# Sheet1.net
KiCad netlist of a schematic drawn in Altium Designer
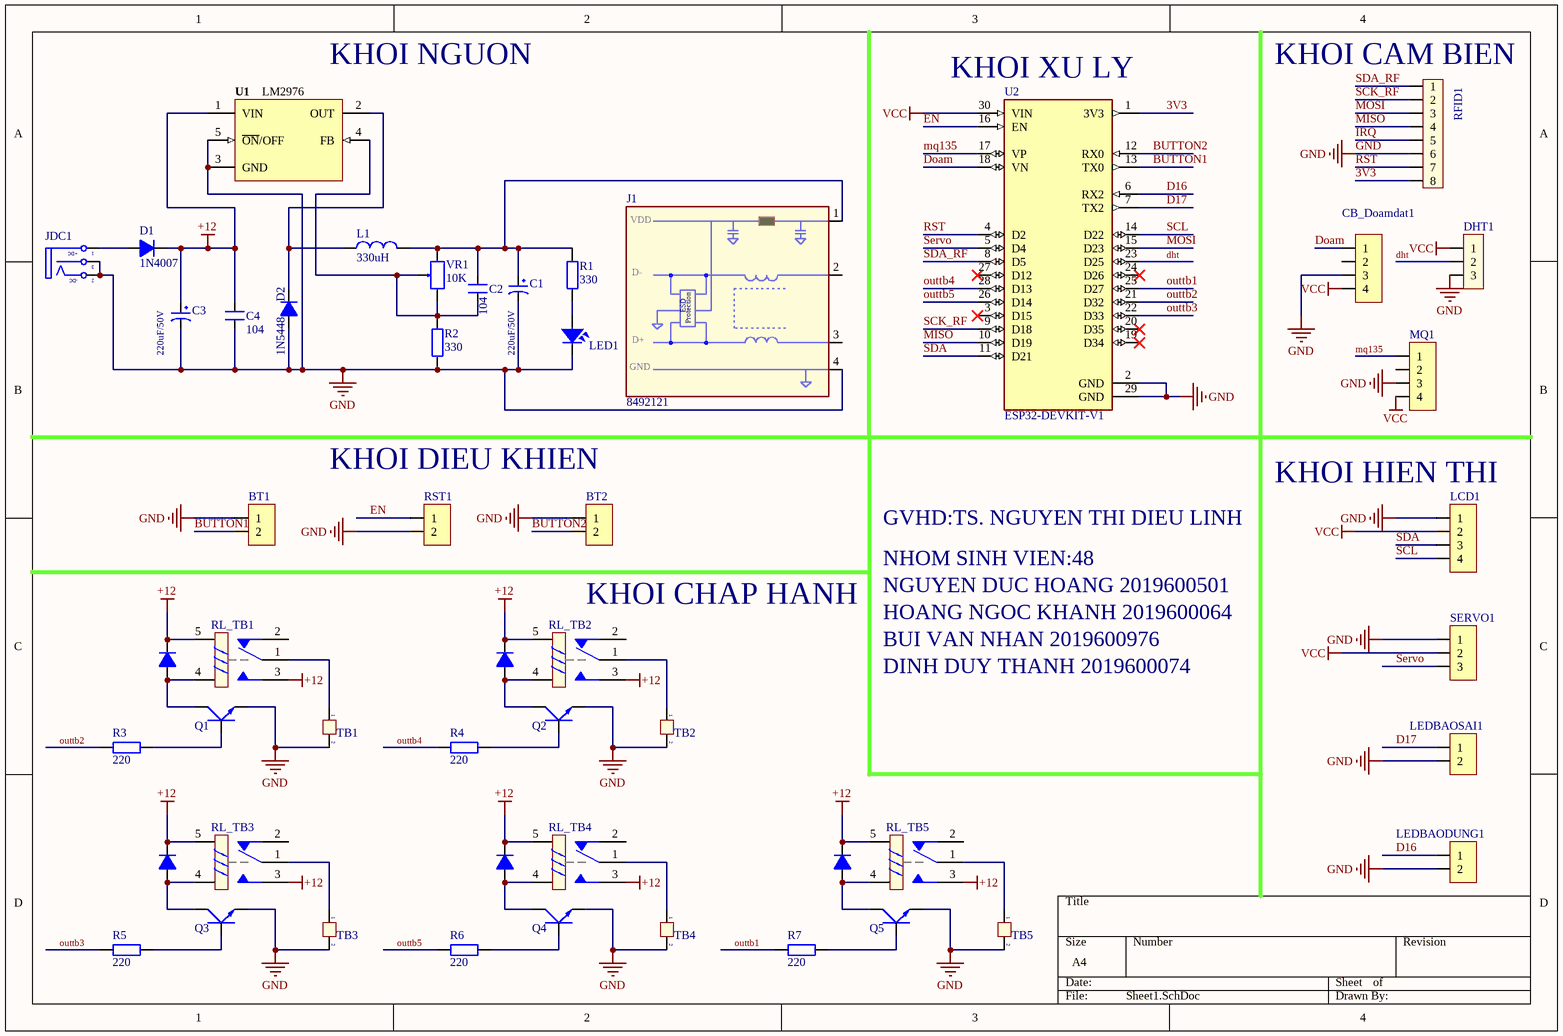
[diagram p0: Sheet1.SchDoc]

(export (version "E")
  (design (tool "Eeschema 10.0.6"))
  (components
    (comp (ref "BT1")
      (value "JP2")
      (footprint "JP2-C1T")
      (description "WR-PHD 2.54 mm Angled Socket Header")
      (fields
        (field (name "MANUFACTURER") "Würth Elektronik eiSos GmbH")
        (field (name "PARTNO") "613002143121")
        (field (name "CREATED BY") "Karrer Zheng")
      )
      (libsource (lib "thuviencuatu") (part "JP2"))
    )
    (comp (ref "BT2")
      (value "JP2")
      (footprint "JP2-C1T")
      (description "WR-PHD 2.54 mm Angled Socket Header")
      (fields
        (field (name "MANUFACTURER") "Würth Elektronik eiSos GmbH")
        (field (name "PARTNO") "613002143121")
        (field (name "CREATED BY") "Karrer Zheng")
      )
      (libsource (lib "thuviencuatu") (part "JP2"))
    )
    (comp (ref "C1")
      (value "220uF/50V")
      (footprint "CP1.5/3.4")
      (description "Cap 1000uF/16V - 220uF/50V")
      (libsource (lib "Thuvien3D") (part "CP4"))
    )
    (comp (ref "C2")
      (value "104")
      (footprint "CN1")
      (description "Cap np  1pF - 472pF")
      (libsource (lib "Thuvien3D") (part "CN1"))
    )
    (comp (ref "C3")
      (value "220uF/50V")
      (footprint "CP1.5/3.4")
      (description "Cap 1000uF/16V - 220uF/50V")
      (libsource (lib "Thuvien3D") (part "CP4"))
    )
    (comp (ref "C4")
      (value "104")
      (footprint "CN1")
      (description "Cap np  1pF - 472pF")
      (libsource (lib "Thuvien3D") (part "CN1"))
    )
    (comp (ref "CB_Doamdat1")
      (value "JP4")
      (footprint "JP4-C1T")
      (description "WR-PHD 2.54 mm Angled Socket Header")
      (fields
        (field (name "MANUFACTURER") "Würth Elektronik eiSos GmbH")
        (field (name "PARTNO") "613004143121")
        (field (name "CREATED BY") "Karrer Zheng")
      )
      (libsource (lib "thuviencuatu") (part "JP4"))
    )
    (comp (ref "D1")
      (value "1N4007")
      (footprint "D1A")
      (description "Diode 1A")
      (libsource (lib "Thuvien3D") (part "D1A"))
    )
    (comp (ref "D2")
      (value "1N5448")
      (footprint "D1A")
      (description "Diode 1A")
      (libsource (lib "Thuvien3D") (part "D1A"))
    )
    (comp (ref "D3")
      (value "1N4007")
      (footprint "D2A")
      (description "Diode 1A")
      (libsource (lib "Thuvien3D") (part "D1A"))
    )
    (comp (ref "D4")
      (value "1N4007")
      (footprint "D2A")
      (description "Diode 1A")
      (libsource (lib "Thuvien3D") (part "D1A"))
    )
    (comp (ref "D5")
      (value "1N4007")
      (footprint "D2A")
      (description "Diode 1A")
      (libsource (lib "Thuvien3D") (part "D1A"))
    )
    (comp (ref "D6")
      (value "1N4007")
      (footprint "D2A")
      (description "Diode 1A")
      (libsource (lib "Thuvien3D") (part "D1A"))
    )
    (comp (ref "D7")
      (value "1N4007")
      (footprint "D2A")
      (description "Diode 1A")
      (libsource (lib "Thuvien3D") (part "D1A"))
    )
    (comp (ref "DHT1") (value "Jumper 3") (footprint "JP3") (libsource (lib "Thuvien3D") (part "JP3")))
    (comp (ref "J1")
      (value "8492121")
      (footprint "USB-C1")
      (description "THT USB 2.0 A Connector WE-EPLE")
      (fields
        (field (name "MANUFACTURER") "Würth Elektronik eiSos GmbH")
        (field (name "CREATED BY") "Christin Otto")
      )
      (libsource (lib "thuviencuatu") (part "USB-4"))
    )
    (comp (ref "JDC1")
      (value "Jac DC")
      (footprint "DC-IN")
      (description "Jac DC input")
      (libsource (lib "Thuvien3D") (part "DCIN"))
    )
    (comp (ref "L1")
      (value "330uH")
      (footprint "L01")
      (description "Inductor")
      (libsource (lib "Thuvien3D") (part "L1"))
    )
    (comp (ref "LCD1")
      (value "JP4")
      (footprint "JP4-C1T")
      (description "WR-PHD 2.54 mm Angled Socket Header")
      (fields
        (field (name "MANUFACTURER") "Würth Elektronik eiSos GmbH")
        (field (name "PARTNO") "613004143121")
        (field (name "CREATED BY") "Karrer Zheng")
      )
      (libsource (lib "thuviencuatu") (part "JP4"))
    )
    (comp (ref "LED1")
      (value "LED")
      (footprint "LED-3")
      (description "LED Single colour Green and Red")
      (libsource (lib "Thuvien3D") (part "LED"))
    )
    (comp (ref "LEDBAODUNG1")
      (value "JP2")
      (footprint "JP2-C1T")
      (description "WR-PHD 2.54 mm Angled Socket Header")
      (fields
        (field (name "MANUFACTURER") "Würth Elektronik eiSos GmbH")
        (field (name "PARTNO") "613002143121")
        (field (name "CREATED BY") "Karrer Zheng")
      )
      (libsource (lib "thuviencuatu") (part "JP2"))
    )
    (comp (ref "LEDBAOSAI1")
      (value "JP2")
      (footprint "JP2-C1T")
      (description "WR-PHD 2.54 mm Angled Socket Header")
      (fields
        (field (name "MANUFACTURER") "Würth Elektronik eiSos GmbH")
        (field (name "PARTNO") "613002143121")
        (field (name "CREATED BY") "Karrer Zheng")
      )
      (libsource (lib "thuviencuatu") (part "JP2"))
    )
    (comp (ref "MQ1")
      (value "JP4")
      (footprint "JP4-C1T")
      (description "WR-PHD 2.54 mm Angled Socket Header")
      (fields
        (field (name "MANUFACTURER") "Würth Elektronik eiSos GmbH")
        (field (name "PARTNO") "613004143121")
        (field (name "CREATED BY") "Karrer Zheng")
      )
      (libsource (lib "thuviencuatu") (part "JP4"))
    )
    (comp (ref "Q1")
      (value "C1815")
      (footprint "QTO-92")
      (description "NPN 600mW, ECB")
      (libsource (lib "Thuvien3D") (part "C1815"))
    )
    (comp (ref "Q2")
      (value "C1815")
      (footprint "QTO-92")
      (description "NPN 600mW, ECB")
      (libsource (lib "Thuvien3D") (part "C1815"))
    )
    (comp (ref "Q3")
      (value "C1815")
      (footprint "QTO-92")
      (description "NPN 600mW, ECB")
      (libsource (lib "Thuvien3D") (part "C1815"))
    )
    (comp (ref "Q4")
      (value "C1815")
      (footprint "QTO-92")
      (description "NPN 600mW, ECB")
      (libsource (lib "Thuvien3D") (part "C1815"))
    )
    (comp (ref "Q5")
      (value "C1815")
      (footprint "QTO-92")
      (description "NPN 600mW, ECB")
      (libsource (lib "Thuvien3D") (part "C1815"))
    )
    (comp (ref "R1")
      (value "330")
      (footprint "R1/2W")
      (description "Resistor 1/4W")
      (libsource (lib "Thuvien3D") (part "R1/4W"))
    )
    (comp (ref "R2")
      (value "330")
      (footprint "R1/2W")
      (description "Resistor 1/4W")
      (libsource (lib "Thuvien3D") (part "R1/4W"))
    )
    (comp (ref "R3")
      (value "220")
      (footprint "R1/2W")
      (description "Resistor 1/4W")
      (libsource (lib "Thuvien3D") (part "R1/4W"))
    )
    (comp (ref "R4")
      (value "220")
      (footprint "R1/2W")
      (description "Resistor 1/4W")
      (libsource (lib "Thuvien3D") (part "R1/4W"))
    )
    (comp (ref "R5")
      (value "220")
      (footprint "R1/2W")
      (description "Resistor 1/4W")
      (libsource (lib "Thuvien3D") (part "R1/4W"))
    )
    (comp (ref "R6")
      (value "220")
      (footprint "R1/2W")
      (description "Resistor 1/4W")
      (libsource (lib "Thuvien3D") (part "R1/4W"))
    )
    (comp (ref "R7")
      (value "220")
      (footprint "R1/2W")
      (description "Resistor 1/4W")
      (libsource (lib "Thuvien3D") (part "R1/4W"))
    )
    (comp (ref "RFID1") (value "JP8 PIN") (footprint "JP8") (libsource (lib "syhaunguyen") (part "JP8")))
    (comp (ref "RL_TB1")
      (value "Relay1")
      (footprint "RL_SPDT_10A")
      (description "Relay SPDT,10A - 12VDC 5 Pin")
      (libsource (lib "Thuvien3D") (part "Relay 1"))
    )
    (comp (ref "RL_TB2")
      (value "Relay1")
      (footprint "RL_SPDT_10A")
      (description "Relay SPDT,10A - 12VDC 5 Pin")
      (libsource (lib "Thuvien3D") (part "Relay 1"))
    )
    (comp (ref "RL_TB3")
      (value "Relay1")
      (footprint "RL_SPDT_10A")
      (description "Relay SPDT,10A - 12VDC 5 Pin")
      (libsource (lib "Thuvien3D") (part "Relay 1"))
    )
    (comp (ref "RL_TB4")
      (value "Relay1")
      (footprint "RL_SPDT_10A")
      (description "Relay SPDT,10A - 12VDC 5 Pin")
      (libsource (lib "Thuvien3D") (part "Relay 1"))
    )
    (comp (ref "RL_TB5")
      (value "Relay1")
      (footprint "RL_SPDT_10A")
      (description "Relay SPDT,10A - 12VDC 5 Pin")
      (libsource (lib "Thuvien3D") (part "Relay 1"))
    )
    (comp (ref "RST1")
      (value "JP2")
      (footprint "JP2-C1T")
      (description "WR-PHD 2.54 mm Angled Socket Header")
      (fields
        (field (name "MANUFACTURER") "Würth Elektronik eiSos GmbH")
        (field (name "PARTNO") "613002143121")
        (field (name "CREATED BY") "Karrer Zheng")
      )
      (libsource (lib "thuviencuatu") (part "JP2"))
    )
    (comp (ref "SERVO1")
      (value "JP3")
      (footprint "JP3-C1T")
      (description "WR-PHD 2.54 mm Angled Socket Header")
      (fields
        (field (name "MANUFACTURER") "Würth Elektronik eiSos GmbH")
        (field (name "PARTNO") "613003143121")
        (field (name "CREATED BY") "Karrer Zheng")
      )
      (libsource (lib "thuviencuatu") (part "JP3"))
    )
    (comp (ref "TB1") (value "Jumper 2") (footprint "JP2") (libsource (lib "Thuvien3D") (part "JP 2")))
    (comp (ref "TB2") (value "Jumper 2") (footprint "JP2") (libsource (lib "Thuvien3D") (part "JP 2")))
    (comp (ref "TB3") (value "Jumper 2") (footprint "JP2") (libsource (lib "Thuvien3D") (part "JP 2")))
    (comp (ref "TB4") (value "Jumper 2") (footprint "JP2") (libsource (lib "Thuvien3D") (part "JP 2")))
    (comp (ref "TB5") (value "Jumper 2") (footprint "JP2") (libsource (lib "Thuvien3D") (part "JP 2")))
    (comp (ref "U1") (value "LM2976") (footprint "DIP5-T") (libsource (lib "thuviencuatu") (part "LM2596")))
    (comp (ref "U2")
      (value "ESP32-DEVKIT-V1")
      (footprint "MODULE_ESP32_DEVKIT_V1")
      (fields (field (name "MF") "Do it"))
      (libsource (lib "ESP32-DEVKIT-V1") (part "ESP32-DEVKIT-V1"))
    )
    (comp (ref "VR1")
      (value "10K")
      (footprint "VR")
      (description "Var Resistor")
      (libsource (lib "Thuvien3D") (part "VR"))
    )
  )
  (nets
    (net (code "1") (name "+12") (class "Default")
      (node (ref "C3") (pin "1") (pinfunction "1_1") (pintype "passive"))
      (node (ref "C4") (pin "2") (pinfunction "2_2") (pintype "passive"))
      (node (ref "D1") (pin "2") (pinfunction "K_2") (pintype "passive"))
      (node (ref "D3") (pin "2") (pinfunction "K_2") (pintype "passive"))
      (node (ref "D4") (pin "2") (pinfunction "K_2") (pintype "passive"))
      (node (ref "D5") (pin "2") (pinfunction "K_2") (pintype "passive"))
      (node (ref "D6") (pin "2") (pinfunction "K_2") (pintype "passive"))
      (node (ref "D7") (pin "2") (pinfunction "K_2") (pintype "passive"))
      (node (ref "RL_TB1") (pin "3") (pinfunction "3_3") (pintype "passive"))
      (node (ref "RL_TB1") (pin "5") (pinfunction "5_5") (pintype "passive"))
      (node (ref "RL_TB2") (pin "3") (pinfunction "3_3") (pintype "passive"))
      (node (ref "RL_TB2") (pin "5") (pinfunction "5_5") (pintype "passive"))
      (node (ref "RL_TB3") (pin "3") (pinfunction "3_3") (pintype "passive"))
      (node (ref "RL_TB3") (pin "5") (pinfunction "5_5") (pintype "passive"))
      (node (ref "RL_TB4") (pin "3") (pinfunction "3_3") (pintype "passive"))
      (node (ref "RL_TB4") (pin "5") (pinfunction "5_5") (pintype "passive"))
      (node (ref "RL_TB5") (pin "3") (pinfunction "3_3") (pintype "passive"))
      (node (ref "RL_TB5") (pin "5") (pinfunction "5_5") (pintype "passive"))
      (node (ref "U1") (pin "1") (pinfunction "VIN_1") (pintype "power_in"))
    )
    (net (code "2") (name "/3V3") (class "Default")
      (node (ref "RFID1") (pin "8") (pinfunction "8_8") (pintype "passive"))
      (node (ref "U2") (pin "1") (pinfunction "3V3_1") (pintype "output"))
    )
    (net (code "3") (name "/BUTTON1") (class "Default")
      (node (ref "BT1") (pin "2") (pinfunction "2_2") (pintype "passive"))
      (node (ref "U2") (pin "13") (pinfunction "TX0_13") (pintype "output"))
    )
    (net (code "4") (name "/BUTTON2") (class "Default")
      (node (ref "BT2") (pin "2") (pinfunction "2_2") (pintype "passive"))
      (node (ref "U2") (pin "12") (pinfunction "RX0_12") (pintype "input"))
    )
    (net (code "5") (name "/D16") (class "Default")
      (node (ref "LEDBAODUNG1") (pin "1") (pinfunction "1_1") (pintype "passive"))
      (node (ref "U2") (pin "6") (pinfunction "RX2_6") (pintype "input"))
    )
    (net (code "6") (name "/D17") (class "Default")
      (node (ref "LEDBAOSAI1") (pin "1") (pinfunction "1_1") (pintype "passive"))
      (node (ref "U2") (pin "7") (pinfunction "TX2_7") (pintype "output"))
    )
    (net (code "7") (name "/Doam") (class "Default")
      (node (ref "CB_Doamdat1") (pin "1") (pinfunction "1_1") (pintype "passive"))
      (node (ref "U2") (pin "18") (pinfunction "VN_18") (pintype "bidirectional"))
    )
    (net (code "8") (name "/EN") (class "Default")
      (node (ref "RST1") (pin "1") (pinfunction "1_1") (pintype "passive"))
      (node (ref "U2") (pin "16") (pinfunction "EN_16") (pintype "input"))
    )
    (net (code "9") (name "/IRQ") (class "Default")
      (node (ref "RFID1") (pin "5") (pinfunction "5_5") (pintype "passive"))
    )
    (net (code "10") (name "/MISO") (class "Default")
      (node (ref "RFID1") (pin "4") (pinfunction "4_4") (pintype "passive"))
      (node (ref "U2") (pin "10") (pinfunction "D19_10") (pintype "bidirectional"))
    )
    (net (code "11") (name "/MOSI") (class "Default")
      (node (ref "RFID1") (pin "3") (pinfunction "3_3") (pintype "passive"))
      (node (ref "U2") (pin "15") (pinfunction "D23_15") (pintype "bidirectional"))
    )
    (net (code "12") (name "/RST") (class "Default")
      (node (ref "RFID1") (pin "7") (pinfunction "7_7") (pintype "passive"))
      (node (ref "U2") (pin "4") (pinfunction "D2_4") (pintype "bidirectional"))
    )
    (net (code "13") (name "/SCK_RF") (class "Default")
      (node (ref "RFID1") (pin "2") (pinfunction "2_2") (pintype "passive"))
      (node (ref "U2") (pin "9") (pinfunction "D18_9") (pintype "bidirectional"))
    )
    (net (code "14") (name "/SCL") (class "Default")
      (node (ref "LCD1") (pin "4") (pinfunction "4_4") (pintype "passive"))
      (node (ref "U2") (pin "14") (pinfunction "D22_14") (pintype "bidirectional"))
    )
    (net (code "15") (name "/SDA") (class "Default")
      (node (ref "LCD1") (pin "3") (pinfunction "3_3") (pintype "passive"))
      (node (ref "U2") (pin "11") (pinfunction "D21_11") (pintype "bidirectional"))
    )
    (net (code "16") (name "/SDA_RF") (class "Default")
      (node (ref "RFID1") (pin "1") (pinfunction "1_1") (pintype "passive"))
      (node (ref "U2") (pin "8") (pinfunction "D5_8") (pintype "bidirectional"))
    )
    (net (code "17") (name "/Servo") (class "Default")
      (node (ref "SERVO1") (pin "3") (pinfunction "3_3") (pintype "passive"))
      (node (ref "U2") (pin "5") (pinfunction "D4_5") (pintype "bidirectional"))
    )
    (net (code "18") (name "/dht") (class "Default")
      (node (ref "DHT1") (pin "2") (pinfunction "2_2") (pintype "passive"))
      (node (ref "U2") (pin "23") (pinfunction "D25_23") (pintype "bidirectional"))
    )
    (net (code "19") (name "/mq135") (class "Default")
      (node (ref "MQ1") (pin "1") (pinfunction "1_1") (pintype "passive"))
      (node (ref "U2") (pin "17") (pinfunction "VP_17") (pintype "bidirectional"))
    )
    (net (code "20") (name "/outtb1") (class "Default")
      (node (ref "R7") (pin "1") (pinfunction "1_1") (pintype "passive"))
      (node (ref "U2") (pin "25") (pinfunction "D27_25") (pintype "bidirectional"))
    )
    (net (code "21") (name "/outtb2") (class "Default")
      (node (ref "R3") (pin "1") (pinfunction "1_1") (pintype "passive"))
      (node (ref "U2") (pin "21") (pinfunction "D32_21") (pintype "bidirectional"))
    )
    (net (code "22") (name "/outtb3") (class "Default")
      (node (ref "R5") (pin "1") (pinfunction "1_1") (pintype "passive"))
      (node (ref "U2") (pin "22") (pinfunction "D33_22") (pintype "bidirectional"))
    )
    (net (code "23") (name "/outtb4") (class "Default")
      (node (ref "R4") (pin "1") (pinfunction "1_1") (pintype "passive"))
      (node (ref "U2") (pin "28") (pinfunction "D13_28") (pintype "bidirectional"))
    )
    (net (code "24") (name "/outtb5") (class "Default")
      (node (ref "R6") (pin "1") (pinfunction "1_1") (pintype "passive"))
      (node (ref "U2") (pin "26") (pinfunction "D14_26") (pintype "bidirectional"))
    )
    (net (code "25") (name "GND") (class "Default")
      (node (ref "BT1") (pin "1") (pinfunction "1_1") (pintype "passive"))
      (node (ref "BT2") (pin "1") (pinfunction "1_1") (pintype "passive"))
      (node (ref "C1") (pin "2") (pinfunction "2_2") (pintype "passive"))
      (node (ref "C3") (pin "2") (pinfunction "2_2") (pintype "passive"))
      (node (ref "C4") (pin "1") (pinfunction "1_1") (pintype "passive"))
      (node (ref "CB_Doamdat1") (pin "3") (pinfunction "3_3") (pintype "passive"))
      (node (ref "D2") (pin "1") (pinfunction "A_1") (pintype "passive"))
      (node (ref "DHT1") (pin "3") (pinfunction "3_3") (pintype "passive"))
      (node (ref "J1") (pin "4") (pinfunction "GND_4") (pintype "passive"))
      (node (ref "JDC1") (pin "2") (pinfunction "TN_2") (pintype "passive"))
      (node (ref "JDC1") (pin "3") (pinfunction "S_3") (pintype "power_in"))
      (node (ref "LCD1") (pin "1") (pinfunction "1_1") (pintype "passive"))
      (node (ref "LED1") (pin "2") (pinfunction "2_2") (pintype "passive"))
      (node (ref "LEDBAODUNG1") (pin "2") (pinfunction "2_2") (pintype "passive"))
      (node (ref "LEDBAOSAI1") (pin "2") (pinfunction "2_2") (pintype "passive"))
      (node (ref "MQ1") (pin "3") (pinfunction "3_3") (pintype "passive"))
      (node (ref "Q1") (pin "1") (pinfunction "E_1") (pintype "passive"))
      (node (ref "Q2") (pin "1") (pinfunction "E_1") (pintype "passive"))
      (node (ref "Q3") (pin "1") (pinfunction "E_1") (pintype "passive"))
      (node (ref "Q4") (pin "1") (pinfunction "E_1") (pintype "passive"))
      (node (ref "Q5") (pin "1") (pinfunction "E_1") (pintype "passive"))
      (node (ref "R2") (pin "1") (pinfunction "1_1") (pintype "passive"))
      (node (ref "RFID1") (pin "6") (pinfunction "6_6") (pintype "passive"))
      (node (ref "RST1") (pin "2") (pinfunction "2_2") (pintype "passive"))
      (node (ref "SERVO1") (pin "1") (pinfunction "1_1") (pintype "passive"))
      (node (ref "TB1") (pin "2") (pinfunction "2_2") (pintype "passive"))
      (node (ref "TB2") (pin "2") (pinfunction "2_2") (pintype "passive"))
      (node (ref "TB3") (pin "2") (pinfunction "2_2") (pintype "passive"))
      (node (ref "TB4") (pin "2") (pinfunction "2_2") (pintype "passive"))
      (node (ref "TB5") (pin "2") (pinfunction "2_2") (pintype "passive"))
      (node (ref "U1") (pin "3") (pinfunction "GND_3") (pintype "power_in"))
      (node (ref "U1") (pin "5") (pinfunction "~{ON}/OFF_5") (pintype "input"))
      (node (ref "U2") (pin "2") (pinfunction "GND_2") (pintype "power_in"))
      (node (ref "U2") (pin "29") (pinfunction "GND_29") (pintype "power_in"))
    )
    (net (code "26") (name "Net-(D1-A)") (class "Default")
      (node (ref "D1") (pin "1") (pinfunction "A_1") (pintype "passive"))
      (node (ref "JDC1") (pin "1") (pinfunction "T_1") (pintype "passive"))
    )
    (net (code "27") (name "Net-(D2-K)") (class "Default")
      (node (ref "D2") (pin "2") (pinfunction "K_2") (pintype "passive"))
      (node (ref "L1") (pin "1") (pinfunction "1_1") (pintype "passive"))
      (node (ref "U1") (pin "2") (pinfunction "OUT_2") (pintype "power_in"))
    )
    (net (code "28") (name "Net-(D3-A)") (class "Default")
      (node (ref "D3") (pin "1") (pinfunction "A_1") (pintype "passive"))
      (node (ref "Q1") (pin "2") (pinfunction "C_2") (pintype "passive"))
      (node (ref "RL_TB1") (pin "4") (pinfunction "4_4") (pintype "passive"))
    )
    (net (code "29") (name "Net-(D4-A)") (class "Default")
      (node (ref "D4") (pin "1") (pinfunction "A_1") (pintype "passive"))
      (node (ref "Q2") (pin "2") (pinfunction "C_2") (pintype "passive"))
      (node (ref "RL_TB2") (pin "4") (pinfunction "4_4") (pintype "passive"))
    )
    (net (code "30") (name "Net-(D5-A)") (class "Default")
      (node (ref "D5") (pin "1") (pinfunction "A_1") (pintype "passive"))
      (node (ref "Q3") (pin "2") (pinfunction "C_2") (pintype "passive"))
      (node (ref "RL_TB3") (pin "4") (pinfunction "4_4") (pintype "passive"))
    )
    (net (code "31") (name "Net-(D6-A)") (class "Default")
      (node (ref "D6") (pin "1") (pinfunction "A_1") (pintype "passive"))
      (node (ref "Q4") (pin "2") (pinfunction "C_2") (pintype "passive"))
      (node (ref "RL_TB4") (pin "4") (pinfunction "4_4") (pintype "passive"))
    )
    (net (code "32") (name "Net-(D7-A)") (class "Default")
      (node (ref "D7") (pin "1") (pinfunction "A_1") (pintype "passive"))
      (node (ref "Q5") (pin "2") (pinfunction "C_2") (pintype "passive"))
      (node (ref "RL_TB5") (pin "4") (pinfunction "4_4") (pintype "passive"))
    )
    (net (code "33") (name "Net-(J1-VBUS)") (class "Default")
      (node (ref "C1") (pin "1") (pinfunction "1_1") (pintype "passive"))
      (node (ref "C2") (pin "2") (pinfunction "2_2") (pintype "passive"))
      (node (ref "J1") (pin "1") (pinfunction "VBUS_1") (pintype "passive"))
      (node (ref "L1") (pin "2") (pinfunction "2_2") (pintype "passive"))
      (node (ref "R1") (pin "2") (pinfunction "2_2") (pintype "passive"))
      (node (ref "VR1") (pin "3") (pinfunction "3_3") (pintype "passive"))
    )
    (net (code "34") (name "Net-(LED1-Pad1)") (class "Default")
      (node (ref "LED1") (pin "1") (pinfunction "1_1") (pintype "passive"))
      (node (ref "R1") (pin "1") (pinfunction "1_1") (pintype "passive"))
    )
    (net (code "35") (name "Net-(Q1-B)") (class "Default")
      (node (ref "Q1") (pin "3") (pinfunction "B_3") (pintype "passive"))
      (node (ref "R3") (pin "2") (pinfunction "2_2") (pintype "passive"))
    )
    (net (code "36") (name "Net-(Q2-B)") (class "Default")
      (node (ref "Q2") (pin "3") (pinfunction "B_3") (pintype "passive"))
      (node (ref "R4") (pin "2") (pinfunction "2_2") (pintype "passive"))
    )
    (net (code "37") (name "Net-(Q3-B)") (class "Default")
      (node (ref "Q3") (pin "3") (pinfunction "B_3") (pintype "passive"))
      (node (ref "R5") (pin "2") (pinfunction "2_2") (pintype "passive"))
    )
    (net (code "38") (name "Net-(Q4-B)") (class "Default")
      (node (ref "Q4") (pin "3") (pinfunction "B_3") (pintype "passive"))
      (node (ref "R6") (pin "2") (pinfunction "2_2") (pintype "passive"))
    )
    (net (code "39") (name "Net-(Q5-B)") (class "Default")
      (node (ref "Q5") (pin "3") (pinfunction "B_3") (pintype "passive"))
      (node (ref "R7") (pin "2") (pinfunction "2_2") (pintype "passive"))
    )
    (net (code "40") (name "Net-(RL_TB1-Pad1)") (class "Default")
      (node (ref "RL_TB1") (pin "1") (pinfunction "1_1") (pintype "passive"))
      (node (ref "TB1") (pin "1") (pinfunction "1_1") (pintype "passive"))
    )
    (net (code "41") (name "Net-(RL_TB2-Pad1)") (class "Default")
      (node (ref "RL_TB2") (pin "1") (pinfunction "1_1") (pintype "passive"))
      (node (ref "TB2") (pin "1") (pinfunction "1_1") (pintype "passive"))
    )
    (net (code "42") (name "Net-(RL_TB3-Pad1)") (class "Default")
      (node (ref "RL_TB3") (pin "1") (pinfunction "1_1") (pintype "passive"))
      (node (ref "TB3") (pin "1") (pinfunction "1_1") (pintype "passive"))
    )
    (net (code "43") (name "Net-(RL_TB4-Pad1)") (class "Default")
      (node (ref "RL_TB4") (pin "1") (pinfunction "1_1") (pintype "passive"))
      (node (ref "TB4") (pin "1") (pinfunction "1_1") (pintype "passive"))
    )
    (net (code "44") (name "Net-(RL_TB5-Pad1)") (class "Default")
      (node (ref "RL_TB5") (pin "1") (pinfunction "1_1") (pintype "passive"))
      (node (ref "TB5") (pin "1") (pinfunction "1_1") (pintype "passive"))
    )
    (net (code "45") (name "Net-(U1-FB)") (class "Default")
      (node (ref "C2") (pin "1") (pinfunction "1_1") (pintype "passive"))
      (node (ref "R2") (pin "2") (pinfunction "2_2") (pintype "passive"))
      (node (ref "U1") (pin "4") (pinfunction "FB_4") (pintype "input"))
      (node (ref "VR1") (pin "1") (pinfunction "1_1") (pintype "passive"))
      (node (ref "VR1") (pin "2") (pinfunction "2_2") (pintype "passive"))
    )
    (net (code "46") (name "VCC") (class "Default")
      (node (ref "CB_Doamdat1") (pin "4") (pinfunction "4_4") (pintype "passive"))
      (node (ref "DHT1") (pin "1") (pinfunction "1_1") (pintype "passive"))
      (node (ref "LCD1") (pin "2") (pinfunction "2_2") (pintype "passive"))
      (node (ref "MQ1") (pin "4") (pinfunction "4_4") (pintype "passive"))
      (node (ref "SERVO1") (pin "2") (pinfunction "2_2") (pintype "passive"))
      (node (ref "U2") (pin "30") (pinfunction "VIN_30") (pintype "input"))
    )
    (net (code "47") (name "unconnected-(CB_Doamdat1-Pad2)") (class "Default")
      (node (ref "CB_Doamdat1") (pin "2") (pinfunction "2_2") (pintype "passive"))
    )
    (net (code "48") (name "unconnected-(J1-D+-Pad3)") (class "Default")
      (node (ref "J1") (pin "3") (pinfunction "D+_3") (pintype "passive"))
    )
    (net (code "49") (name "unconnected-(J1-D--Pad2)") (class "Default")
      (node (ref "J1") (pin "2") (pinfunction "D-_2") (pintype "passive"))
    )
    (net (code "50") (name "unconnected-(MQ1-Pad2)") (class "Default")
      (node (ref "MQ1") (pin "2") (pinfunction "2_2") (pintype "passive"))
    )
    (net (code "51") (name "unconnected-(RL_TB1-Pad2)") (class "Default")
      (node (ref "RL_TB1") (pin "2") (pinfunction "2_2") (pintype "passive"))
    )
    (net (code "52") (name "unconnected-(RL_TB2-Pad2)") (class "Default")
      (node (ref "RL_TB2") (pin "2") (pinfunction "2_2") (pintype "passive"))
    )
    (net (code "53") (name "unconnected-(RL_TB3-Pad2)") (class "Default")
      (node (ref "RL_TB3") (pin "2") (pinfunction "2_2") (pintype "passive"))
    )
    (net (code "54") (name "unconnected-(RL_TB4-Pad2)") (class "Default")
      (node (ref "RL_TB4") (pin "2") (pinfunction "2_2") (pintype "passive"))
    )
    (net (code "55") (name "unconnected-(RL_TB5-Pad2)") (class "Default")
      (node (ref "RL_TB5") (pin "2") (pinfunction "2_2") (pintype "passive"))
    )
    (net (code "56") (name "unconnected-(U2-D12-Pad27)") (class "Default")
      (node (ref "U2") (pin "27") (pinfunction "D12_27") (pintype "bidirectional+no_connect"))
    )
    (net (code "57") (name "unconnected-(U2-D15-Pad3)") (class "Default")
      (node (ref "U2") (pin "3") (pinfunction "D15_3") (pintype "bidirectional+no_connect"))
    )
    (net (code "58") (name "unconnected-(U2-D26-Pad24)") (class "Default")
      (node (ref "U2") (pin "24") (pinfunction "D26_24") (pintype "bidirectional+no_connect"))
    )
    (net (code "59") (name "unconnected-(U2-D34-Pad19)") (class "Default")
      (node (ref "U2") (pin "19") (pinfunction "D34_19") (pintype "bidirectional+no_connect"))
    )
    (net (code "60") (name "unconnected-(U2-D35-Pad20)") (class "Default")
      (node (ref "U2") (pin "20") (pinfunction "D35_20") (pintype "bidirectional+no_connect"))
    )
  )
)
